# BB_001_01_20_3.net
KiCad netlist of a schematic drawn in Altium Designer
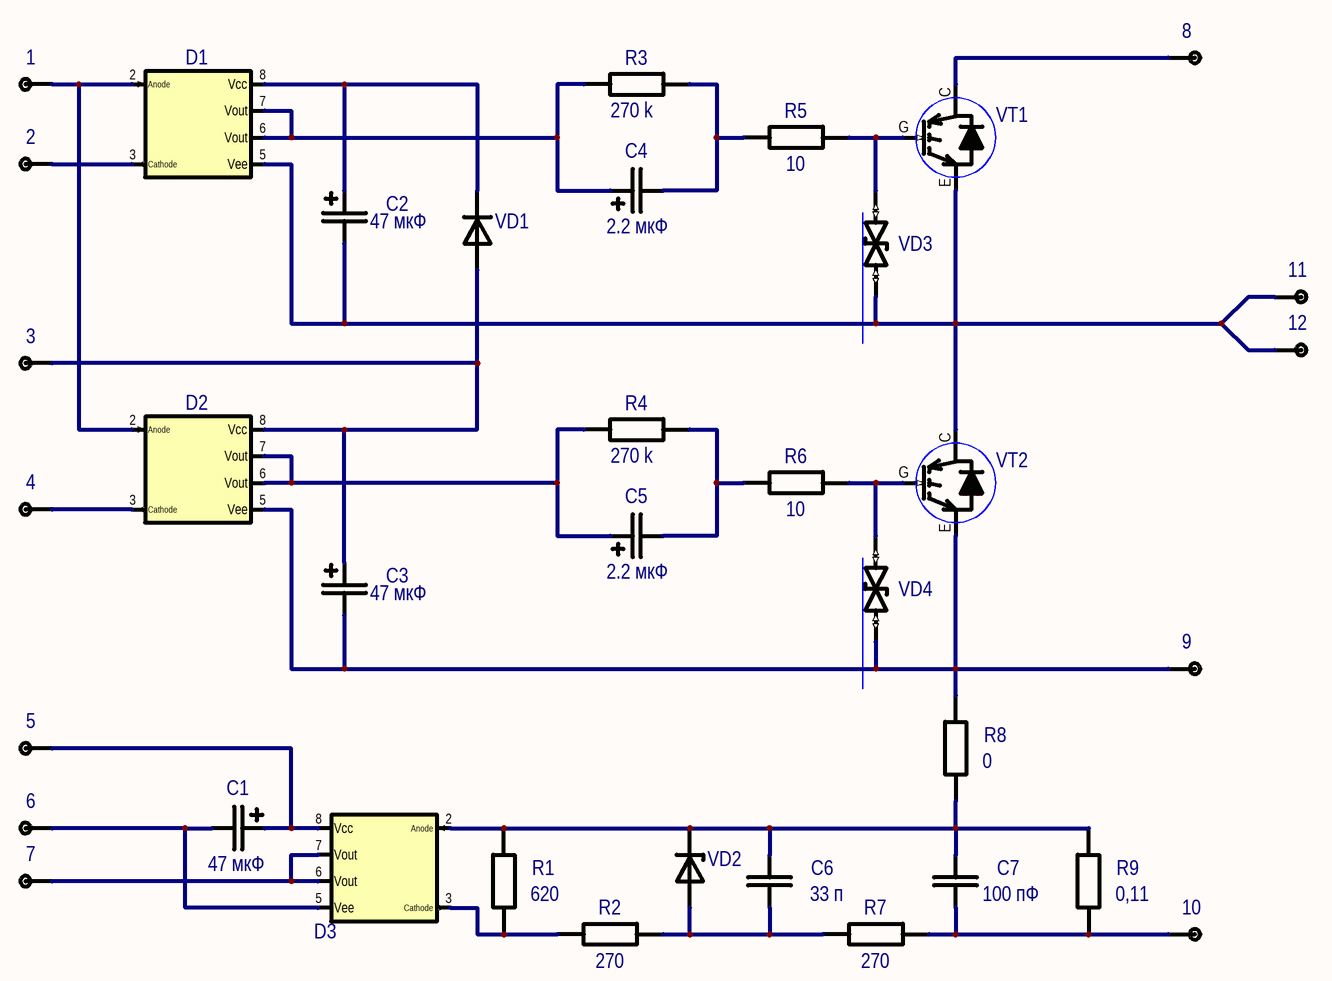
[diagram p0: BB.001.01.20 Э3 (Силовой модуль).SchDoc]

(export (version "E")
  (design (tool "Eeschema 10.0.6"))
  (components
    (comp (ref "1")
      (value "TP")
      (footprint "TP1")
      (description "Test point")
      (libsource (lib "BB.001") (part "TP"))
    )
    (comp (ref "2")
      (value "TP")
      (footprint "TP1")
      (description "Test point")
      (libsource (lib "BB.001") (part "TP"))
    )
    (comp (ref "3")
      (value "TP")
      (footprint "TP1")
      (description "Test point")
      (libsource (lib "BB.001") (part "TP"))
    )
    (comp (ref "4")
      (value "TP")
      (footprint "TP1")
      (description "Test point")
      (libsource (lib "BB.001") (part "TP"))
    )
    (comp (ref "5")
      (value "TP")
      (footprint "TP1")
      (description "Test point")
      (libsource (lib "BB.001") (part "TP"))
    )
    (comp (ref "6")
      (value "TP")
      (footprint "TP1")
      (description "Test point")
      (libsource (lib "BB.001") (part "TP"))
    )
    (comp (ref "7")
      (value "TP")
      (footprint "TP1")
      (description "Test point")
      (libsource (lib "BB.001") (part "TP"))
    )
    (comp (ref "8")
      (value "TP")
      (footprint "TP1")
      (description "Test point")
      (libsource (lib "BB.001") (part "TP"))
    )
    (comp (ref "9")
      (value "TP")
      (footprint "TP1")
      (description "Test point")
      (libsource (lib "BB.001") (part "TP"))
    )
    (comp (ref "10")
      (value "TP")
      (footprint "TP1")
      (description "Test point")
      (libsource (lib "BB.001") (part "TP"))
    )
    (comp (ref "11")
      (value "TP")
      (footprint "TP1")
      (description "Test point")
      (libsource (lib "BB.001") (part "TP"))
    )
    (comp (ref "12")
      (value "TP")
      (footprint "TP1")
      (description "Test point")
      (libsource (lib "BB.001") (part "TP"))
    )
    (comp (ref "C1")
      (value "47 мкФ")
      (footprint "CAPMP7343X31N")
      (description "Танталовый конденсатор")
      (fields (field (name "TOLERANCE") "{Tolerance}"))
      (libsource (lib "BB.001") (part "Capacitor_Polar_TAJD"))
    )
    (comp (ref "C2")
      (value "47 мкФ")
      (footprint "CAPMP7343X31N")
      (description "Танталовый конденсатор")
      (fields (field (name "TOLERANCE") "{Tolerance}"))
      (libsource (lib "BB.001") (part "Capacitor_Polar_TAJD"))
    )
    (comp (ref "C3")
      (value "47 мкФ")
      (footprint "CAPMP7343X31N")
      (description "Танталовый конденсатор")
      (fields (field (name "TOLERANCE") "{Tolerance}"))
      (libsource (lib "BB.001") (part "Capacitor_Polar_TAJD"))
    )
    (comp (ref "C4")
      (value "2.2 мкФ")
      (footprint "CAPMP7343X31N")
      (description "Танталовый конденсатор")
      (fields (field (name "TOLERANCE") "{Tolerance}"))
      (libsource (lib "BB.001") (part "Capacitor_Polar_TAJD"))
    )
    (comp (ref "C5")
      (value "2.2 мкФ")
      (footprint "CAPMP7343X31N")
      (description "Танталовый конденсатор")
      (fields (field (name "TOLERANCE") "{Tolerance}"))
      (libsource (lib "BB.001") (part "Capacitor_Polar_TAJD"))
    )
    (comp (ref "C6")
      (value "33 п")
      (footprint "CAPC1632X115M")
      (description "Чип-конденсатор")
      (fields (field (name "TOLERANCE") "{Tolerance}"))
      (libsource (lib "BB.001") (part "Capacitor_Chip"))
    )
    (comp (ref "C7")
      (value "100 пФ")
      (footprint "CAPC1608M")
      (description "Чип-конденсатор")
      (fields (field (name "TOLERANCE") "{Tolerance}"))
      (libsource (lib "BB.001") (part "Capacitor_Chip"))
    )
    (comp (ref "D1")
      (value "МикросхемаHCPL-3120")
      (footprint "DIP-8")
      (description "2.5 Amp Output Current IGBT Gate Drive Optocoupler")
      (fields
        (field (name "MANUFACTURERPARTNUMBER") "HCPL-3120")
        (field (name "MANUFACTURER") "Avago, Avago Technologies")
        (field (name "COMPONENTLINK1URL") "k:\\Projects\\BB.001.00.00 (Преобразователь частотный)\\Datashets\\Функциональная группа ''A1''\\hcpl-3120-500e.pdf")
        (field (name "COMPONENTLINK2URL") "k:\\Projects\\BB.001.00.00 (Преобразователь частотный)\\Datashets\\Функциональная группа ''A1''\\hcpl-3120-500e.pdf#page=3")
      )
      (libsource (lib "") (part "Device_HCPL-3120_1"))
    )
    (comp (ref "D2")
      (value "МикросхемаHCPL-3120")
      (footprint "DIP-8")
      (description "2.5 Amp Output Current IGBT Gate Drive Optocoupler")
      (fields
        (field (name "MANUFACTURERPARTNUMBER") "HCPL-3120")
        (field (name "MANUFACTURER") "Avago, Avago Technologies")
        (field (name "COMPONENTLINK1URL") "k:\\Projects\\BB.001.00.00 (Преобразователь частотный)\\Datashets\\Функциональная группа ''A1''\\hcpl-3120-500e.pdf")
        (field (name "COMPONENTLINK2URL") "k:\\Projects\\BB.001.00.00 (Преобразователь частотный)\\Datashets\\Функциональная группа ''A1''\\hcpl-3120-500e.pdf#page=3")
      )
      (libsource (lib "") (part "Device_HCPL-3120_1"))
    )
    (comp (ref "D3")
      (value "МикросхемаHCPL-3120")
      (footprint "DIP-8")
      (description "2.5 Amp Output Current IGBT Gate Drive Optocoupler")
      (fields
        (field (name "MANUFACTURERPARTNUMBER") "HCPL-3120")
        (field (name "MANUFACTURER") "Avago, Avago Technologies")
        (field (name "COMPONENTLINK1URL") "k:\\Projects\\BB.001.00.00 (Преобразователь частотный)\\Datashets\\Функциональная группа ''A1''\\hcpl-3120-500e.pdf")
        (field (name "COMPONENTLINK2URL") "k:\\Projects\\BB.001.00.00 (Преобразователь частотный)\\Datashets\\Функциональная группа ''A1''\\hcpl-3120-500e.pdf#page=3")
      )
      (libsource (lib "BB.001") (part "Device_HCPL-3120"))
    )
    (comp (ref "R1")
      (value "620")
      (footprint "RESC3216N")
      (description "Чип-резистор")
      (fields (field (name "TOLERANCE") "{Tolerance}"))
      (libsource (lib "BB.001") (part "Resistor_Chip"))
    )
    (comp (ref "R2")
      (value "270")
      (footprint "RESC3216N")
      (description "Чип-резистор")
      (fields (field (name "TOLERANCE") "{Tolerance}"))
      (libsource (lib "BB.001") (part "Resistor_Chip"))
    )
    (comp (ref "R3")
      (value "270 k")
      (footprint "RESC3216N")
      (description "Чип-резистор")
      (fields (field (name "TOLERANCE") "{Tolerance}"))
      (libsource (lib "BB.001") (part "Resistor_Chip"))
    )
    (comp (ref "R4")
      (value "270 k")
      (footprint "RESC3216N")
      (description "Чип-резистор")
      (fields (field (name "TOLERANCE") "{Tolerance}"))
      (libsource (lib "BB.001") (part "Resistor_Chip"))
    )
    (comp (ref "R5")
      (value "10")
      (footprint "RESC3216N")
      (description "Чип-резистор")
      (fields (field (name "TOLERANCE") "{Tolerance}"))
      (libsource (lib "BB.001") (part "Resistor_Chip"))
    )
    (comp (ref "R6")
      (value "10")
      (footprint "RESC3216N")
      (description "Чип-резистор")
      (fields (field (name "TOLERANCE") "{Tolerance}"))
      (libsource (lib "BB.001") (part "Resistor_Chip"))
    )
    (comp (ref "R7")
      (value "270")
      (footprint "RESC3216N")
      (description "Чип-резистор")
      (fields (field (name "TOLERANCE") "{Tolerance}"))
      (libsource (lib "BB.001") (part "Resistor_Chip"))
    )
    (comp (ref "R8")
      (value "0")
      (footprint "RESC3216N")
      (description "Чип-резистор")
      (fields (field (name "TOLERANCE") "{Tolerance}"))
      (libsource (lib "BB.001") (part "Resistor_Chip"))
    )
    (comp (ref "R9")
      (value "0,11")
      (footprint "RESC3216N")
      (description "Чип-резистор")
      (fields (field (name "TOLERANCE") "{Tolerance}"))
      (libsource (lib "BB.001") (part "Resistor_Chip"))
    )
    (comp (ref "VD1")
      (value "FR20")
      (footprint "DO-15")
      (description "Диод")
      (fields (field (name "MANUFACTURER") "WTE power Semiconductor"))
      (libsource (lib "BB.001") (part "Diode_FR20..Serial"))
    )
    (comp (ref "VD2")
      (value "BZX5V1")
      (footprint "DO-35")
      (description "Диод")
      (fields (field (name "MANUFACTURER") "WTE power Semiconductor"))
      (libsource (lib "BB.001") (part "Diode_BZX5V1"))
    )
    (comp (ref "VD3")
      (value "Stabistor_P6KE15CA")
      (footprint "D2A")
      (description "Стабилитрон")
      (fields (field (name "MANUFACTURERPARTNUMBER") "P6KE15CA"))
      (libsource (lib "BB.001") (part "Stabistor_P6KE15CA"))
    )
    (comp (ref "VD4")
      (value "Stabistor_P6KE15CA")
      (footprint "D2A")
      (description "Стабилитрон")
      (fields (field (name "MANUFACTURERPARTNUMBER") "P6KE15CA"))
      (libsource (lib "BB.001") (part "Stabistor_P6KE15CA"))
    )
    (comp (ref "VT1")
      (value "IGBT_IRG7PH42UD2PDF")
      (footprint "TO-247AC")
      (description "insulated gate bipolar transistor with  ultrafast soft recovery diode")
      (fields (field (name "MANUFACTURERPARTNUMBER") "IRG7PH42UD2PDF"))
      (libsource (lib "BB.001") (part "IGBT_IRG7PH42UD2PDF"))
    )
    (comp (ref "VT2")
      (value "IGBT_IRG7PH42UD2PDF")
      (footprint "TO-247AC")
      (description "insulated gate bipolar transistor with  ultrafast soft recovery diode")
      (fields (field (name "MANUFACTURERPARTNUMBER") "IRG7PH42UD2PDF"))
      (libsource (lib "BB.001") (part "IGBT_IRG7PH42UD2PDF"))
    )
  )
  (nets
    (net (code "1") (name "Net-(7-Pad1)") (class "Default")
      (node (ref "7") (pin "1") (pinfunction "1_1") (pintype "passive"))
      (node (ref "D3") (pin "6") (pinfunction "Vout_6") (pintype "power_in"))
      (node (ref "D3") (pin "7") (pinfunction "Vout_7") (pintype "power_in"))
    )
    (net (code "2") (name "Net-(8-Pad1)") (class "Default")
      (node (ref "8") (pin "1") (pinfunction "1_1") (pintype "passive"))
      (node (ref "VT1") (pin "C") (pinfunction "C_C") (pintype "open_collector"))
    )
    (net (code "3") (name "Net-(10-Pad1)") (class "Default")
      (node (ref "10") (pin "1") (pinfunction "1_1") (pintype "passive"))
      (node (ref "C7") (pin "2") (pinfunction "2_2") (pintype "passive"))
      (node (ref "R7") (pin "2") (pinfunction "2_2") (pintype "passive"))
      (node (ref "R9") (pin "1") (pinfunction "1_1") (pintype "passive"))
    )
    (net (code "4") (name "Net-(C4-Pad1)") (class "Default")
      (node (ref "C4") (pin "1") (pinfunction "1_1") (pintype "passive"))
      (node (ref "R3") (pin "2") (pinfunction "2_2") (pintype "passive"))
      (node (ref "R5") (pin "1") (pinfunction "1_1") (pintype "passive"))
    )
    (net (code "5") (name "Net-(C4-Pad2)") (class "Default")
      (node (ref "C4") (pin "2") (pinfunction "2_2") (pintype "passive"))
      (node (ref "D1") (pin "6") (pinfunction "Vout_6") (pintype "power_in"))
      (node (ref "D1") (pin "7") (pinfunction "Vout_7") (pintype "power_in"))
      (node (ref "R3") (pin "1") (pinfunction "1_1") (pintype "passive"))
    )
    (net (code "6") (name "Net-(C5-Pad1)") (class "Default")
      (node (ref "C5") (pin "1") (pinfunction "1_1") (pintype "passive"))
      (node (ref "R4") (pin "2") (pinfunction "2_2") (pintype "passive"))
      (node (ref "R6") (pin "1") (pinfunction "1_1") (pintype "passive"))
    )
    (net (code "7") (name "Net-(C5-Pad2)") (class "Default")
      (node (ref "C5") (pin "2") (pinfunction "2_2") (pintype "passive"))
      (node (ref "D2") (pin "6") (pinfunction "Vout_6") (pintype "power_in"))
      (node (ref "D2") (pin "7") (pinfunction "Vout_7") (pintype "power_in"))
      (node (ref "R4") (pin "1") (pinfunction "1_1") (pintype "passive"))
    )
    (net (code "8") (name "Net-(D1-Anode)") (class "Default")
      (node (ref "1") (pin "1") (pinfunction "1_1") (pintype "passive"))
      (node (ref "D1") (pin "2") (pinfunction "Anode_2") (pintype "input"))
      (node (ref "D2") (pin "2") (pinfunction "Anode_2") (pintype "input"))
    )
    (net (code "9") (name "Net-(D1-Cathode)") (class "Default")
      (node (ref "2") (pin "1") (pinfunction "1_1") (pintype "passive"))
      (node (ref "D1") (pin "3") (pinfunction "Cathode_3") (pintype "output"))
    )
    (net (code "10") (name "Net-(D1-Vcc)") (class "Default")
      (node (ref "C2") (pin "2") (pinfunction "2_2") (pintype "passive"))
      (node (ref "D1") (pin "8") (pinfunction "Vcc_8") (pintype "power_in"))
      (node (ref "VD1") (pin "2") (pinfunction "Cathode_2") (pintype "passive"))
    )
    (net (code "11") (name "Net-(D1-Vee)") (class "Default")
      (node (ref "11") (pin "1") (pinfunction "1_1") (pintype "passive"))
      (node (ref "12") (pin "1") (pinfunction "1_1") (pintype "passive"))
      (node (ref "C2") (pin "1") (pinfunction "1_1") (pintype "passive"))
      (node (ref "D1") (pin "5") (pinfunction "Vee_5") (pintype "power_in"))
      (node (ref "VD3") (pin "1") (pinfunction "Anode_1") (pintype "bidirectional"))
      (node (ref "VT1") (pin "E") (pinfunction "E_E") (pintype "open_emitter"))
      (node (ref "VT2") (pin "C") (pinfunction "C_C") (pintype "open_collector"))
    )
    (net (code "12") (name "Net-(D2-Cathode)") (class "Default")
      (node (ref "4") (pin "1") (pinfunction "1_1") (pintype "passive"))
      (node (ref "D2") (pin "3") (pinfunction "Cathode_3") (pintype "output"))
    )
    (net (code "13") (name "Net-(D2-Vcc)") (class "Default")
      (node (ref "3") (pin "1") (pinfunction "1_1") (pintype "passive"))
      (node (ref "C3") (pin "2") (pinfunction "2_2") (pintype "passive"))
      (node (ref "D2") (pin "8") (pinfunction "Vcc_8") (pintype "power_in"))
      (node (ref "VD1") (pin "1") (pinfunction "Anode_1") (pintype "passive"))
    )
    (net (code "14") (name "Net-(D2-Vee)") (class "Default")
      (node (ref "9") (pin "1") (pinfunction "1_1") (pintype "passive"))
      (node (ref "C3") (pin "1") (pinfunction "1_1") (pintype "passive"))
      (node (ref "D2") (pin "5") (pinfunction "Vee_5") (pintype "power_in"))
      (node (ref "R8") (pin "2") (pinfunction "2_2") (pintype "passive"))
      (node (ref "VD4") (pin "1") (pinfunction "Anode_1") (pintype "bidirectional"))
      (node (ref "VT2") (pin "E") (pinfunction "E_E") (pintype "open_emitter"))
    )
    (net (code "15") (name "Net-(D3-Anode)") (class "Default")
      (node (ref "C6") (pin "1") (pinfunction "1_1") (pintype "passive"))
      (node (ref "C7") (pin "1") (pinfunction "1_1") (pintype "passive"))
      (node (ref "D3") (pin "2") (pinfunction "Anode_2") (pintype "input"))
      (node (ref "R1") (pin "2") (pinfunction "2_2") (pintype "passive"))
      (node (ref "R8") (pin "1") (pinfunction "1_1") (pintype "passive"))
      (node (ref "R9") (pin "2") (pinfunction "2_2") (pintype "passive"))
      (node (ref "VD2") (pin "2") (pinfunction "Cathode_2") (pintype "passive"))
    )
    (net (code "16") (name "Net-(D3-Cathode)") (class "Default")
      (node (ref "D3") (pin "3") (pinfunction "Cathode_3") (pintype "output"))
      (node (ref "R1") (pin "1") (pinfunction "1_1") (pintype "passive"))
      (node (ref "R2") (pin "1") (pinfunction "1_1") (pintype "passive"))
    )
    (net (code "17") (name "Net-(D3-Vcc)") (class "Default")
      (node (ref "5") (pin "1") (pinfunction "1_1") (pintype "passive"))
      (node (ref "C1") (pin "2") (pinfunction "2_2") (pintype "passive"))
      (node (ref "D3") (pin "8") (pinfunction "Vcc_8") (pintype "power_in"))
    )
    (net (code "18") (name "Net-(D3-Vee)") (class "Default")
      (node (ref "6") (pin "1") (pinfunction "1_1") (pintype "passive"))
      (node (ref "C1") (pin "1") (pinfunction "1_1") (pintype "passive"))
      (node (ref "D3") (pin "5") (pinfunction "Vee_5") (pintype "power_in"))
    )
    (net (code "19") (name "Net-(VD2-Anode)") (class "Default")
      (node (ref "C6") (pin "2") (pinfunction "2_2") (pintype "passive"))
      (node (ref "R2") (pin "2") (pinfunction "2_2") (pintype "passive"))
      (node (ref "R7") (pin "1") (pinfunction "1_1") (pintype "passive"))
      (node (ref "VD2") (pin "1") (pinfunction "Anode_1") (pintype "passive"))
    )
    (net (code "20") (name "Net-(VD3-Cathode)") (class "Default")
      (node (ref "R5") (pin "2") (pinfunction "2_2") (pintype "passive"))
      (node (ref "VD3") (pin "2") (pinfunction "Cathode_2") (pintype "bidirectional"))
      (node (ref "VT1") (pin "G") (pinfunction "G_G") (pintype "input"))
    )
    (net (code "21") (name "Net-(VD4-Cathode)") (class "Default")
      (node (ref "R6") (pin "2") (pinfunction "2_2") (pintype "passive"))
      (node (ref "VD4") (pin "2") (pinfunction "Cathode_2") (pintype "bidirectional"))
      (node (ref "VT2") (pin "G") (pinfunction "G_G") (pintype "input"))
    )
  )
)
